# design.net
KiCad netlist of a schematic drawn in Altium Designer
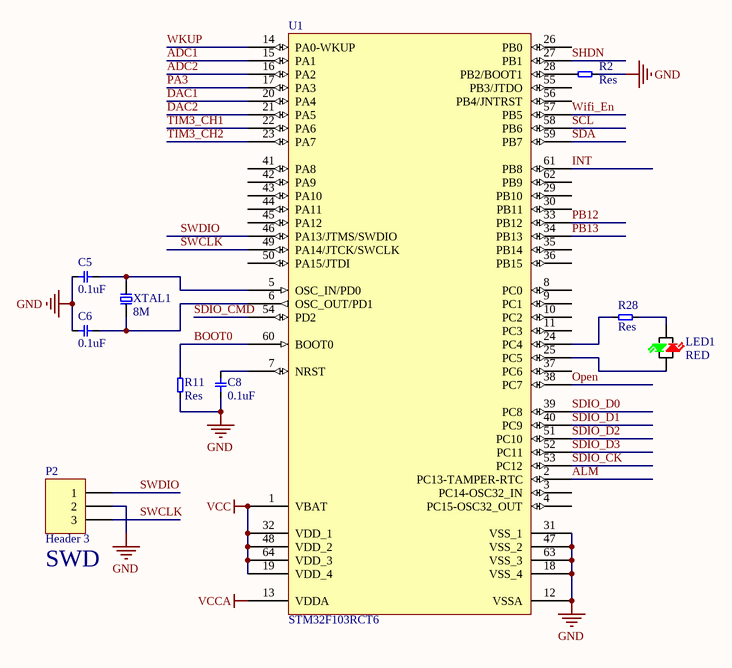
[diagram p0: 原理图.SchDoc]

(export (version "E")
  (design (tool "Eeschema 10.0.6"))
  (components
    (comp (ref "C5") (value "0.1uF") (footprint "0603") (libsource (lib "MySchLib") (part "C0.1uF")))
    (comp (ref "C6") (value "0.1uF") (footprint "0603") (libsource (lib "MySchLib") (part "C0.1uF")))
    (comp (ref "C8") (value "0.1uF") (footprint "0603") (libsource (lib "MySchLib") (part "C0.1uF")))
    (comp (ref "LED1") (value "RED") (footprint "LED2") (libsource (lib "MySchLib") (part "LED_2")))
    (comp (ref "P2")
      (value "Header 3")
      (footprint "HDR1X3-150")
      (description "Header, 3-Pin")
      (fields (field (name "PUBLISHER") "Altium Limited"))
      (libsource (lib "Miscellaneous Connectors") (part "Header 3"))
    )
    (comp (ref "R2") (value "Res") (footprint "0603") (libsource (lib "MySchLib") (part "Res")))
    (comp (ref "R11") (value "Res") (footprint "0603") (libsource (lib "MySchLib") (part "Res")))
    (comp (ref "R28") (value "Res") (footprint "0603") (libsource (lib "MySchLib") (part "Res")))
    (comp (ref "U1")
      (value "STM32F103RCT6")
      (footprint "LQFP64_N")
      (description "STM32 ARM-based 32-bit MCU with 128 Kbytes Flash, 64-pin LQFP, Industrial Temperature")
      (fields (field (name "PUBLISHER") "Altium Limited"))
      (libsource (lib "ST Microcontroller 32-Bit STM32") (part "STM32F103RBT6"))
    )
    (comp (ref "XTAL1") (value "8M") (footprint "XTAL") (libsource (lib "MySchLib") (part "XTAL")))
  )
  (nets
    (net (code "1") (name "/ADC1") (class "Default")
      (node (ref "U1") (pin "15") (pinfunction "PA1_15") (pintype "bidirectional"))
    )
    (net (code "2") (name "/ADC2") (class "Default")
      (node (ref "U1") (pin "16") (pinfunction "PA2_16") (pintype "bidirectional"))
    )
    (net (code "3") (name "/ALM") (class "Default")
      (node (ref "U1") (pin "2") (pinfunction "PC13-TAMPER-RTC_2") (pintype "bidirectional"))
    )
    (net (code "4") (name "/BOOT0") (class "Default")
      (node (ref "R11") (pin "2") (pinfunction "2_2") (pintype "passive"))
      (node (ref "U1") (pin "60") (pinfunction "BOOT0_60") (pintype "input"))
    )
    (net (code "5") (name "/DAC1") (class "Default")
      (node (ref "U1") (pin "20") (pinfunction "PA4_20") (pintype "bidirectional"))
    )
    (net (code "6") (name "/DAC2") (class "Default")
      (node (ref "U1") (pin "21") (pinfunction "PA5_21") (pintype "bidirectional"))
    )
    (net (code "7") (name "/INT") (class "Default")
      (node (ref "U1") (pin "61") (pinfunction "PB8_61") (pintype "bidirectional"))
    )
    (net (code "8") (name "/Open") (class "Default")
      (node (ref "U1") (pin "38") (pinfunction "PC7_38") (pintype "bidirectional"))
    )
    (net (code "9") (name "/PA3") (class "Default")
      (node (ref "U1") (pin "17") (pinfunction "PA3_17") (pintype "bidirectional"))
    )
    (net (code "10") (name "/PB12") (class "Default")
      (node (ref "U1") (pin "33") (pinfunction "PB12_33") (pintype "bidirectional"))
    )
    (net (code "11") (name "/PB13") (class "Default")
      (node (ref "U1") (pin "34") (pinfunction "PB13_34") (pintype "bidirectional"))
    )
    (net (code "12") (name "/SCL") (class "Default")
      (node (ref "U1") (pin "58") (pinfunction "PB6_58") (pintype "bidirectional"))
    )
    (net (code "13") (name "/SDA") (class "Default")
      (node (ref "U1") (pin "59") (pinfunction "PB7_59") (pintype "bidirectional"))
    )
    (net (code "14") (name "/SDIO_CK") (class "Default")
      (node (ref "U1") (pin "53") (pinfunction "PC12_53") (pintype "bidirectional"))
    )
    (net (code "15") (name "/SDIO_CMD") (class "Default")
      (node (ref "U1") (pin "54") (pinfunction "PD2_54") (pintype "bidirectional"))
    )
    (net (code "16") (name "/SDIO_D0") (class "Default")
      (node (ref "U1") (pin "39") (pinfunction "PC8_39") (pintype "bidirectional"))
    )
    (net (code "17") (name "/SDIO_D1") (class "Default")
      (node (ref "U1") (pin "40") (pinfunction "PC9_40") (pintype "bidirectional"))
    )
    (net (code "18") (name "/SDIO_D2") (class "Default")
      (node (ref "U1") (pin "51") (pinfunction "PC10_51") (pintype "bidirectional"))
    )
    (net (code "19") (name "/SDIO_D3") (class "Default")
      (node (ref "U1") (pin "52") (pinfunction "PC11_52") (pintype "bidirectional"))
    )
    (net (code "20") (name "/SHDN") (class "Default")
      (node (ref "U1") (pin "27") (pinfunction "PB1_27") (pintype "bidirectional"))
    )
    (net (code "21") (name "/SWCLK") (class "Default")
      (node (ref "P2") (pin "3") (pinfunction "3_3") (pintype "passive"))
      (node (ref "U1") (pin "49") (pinfunction "PA14/JTCK/SWCLK_49") (pintype "bidirectional"))
    )
    (net (code "22") (name "/SWDIO") (class "Default")
      (node (ref "P2") (pin "1") (pinfunction "1_1") (pintype "passive"))
      (node (ref "U1") (pin "46") (pinfunction "PA13/JTMS/SWDIO_46") (pintype "bidirectional"))
    )
    (net (code "23") (name "/TIM3_CH1") (class "Default")
      (node (ref "U1") (pin "22") (pinfunction "PA6_22") (pintype "bidirectional"))
    )
    (net (code "24") (name "/TIM3_CH2") (class "Default")
      (node (ref "U1") (pin "23") (pinfunction "PA7_23") (pintype "bidirectional"))
    )
    (net (code "25") (name "/WKUP") (class "Default")
      (node (ref "U1") (pin "14") (pinfunction "PA0-WKUP_14") (pintype "bidirectional"))
    )
    (net (code "26") (name "/Wifi_En") (class "Default")
      (node (ref "U1") (pin "57") (pinfunction "PB5_57") (pintype "bidirectional"))
    )
    (net (code "27") (name "GND") (class "Default")
      (node (ref "C5") (pin "1") (pinfunction "1_1") (pintype "passive"))
      (node (ref "C6") (pin "1") (pinfunction "1_1") (pintype "passive"))
      (node (ref "C8") (pin "1") (pinfunction "1_1") (pintype "passive"))
      (node (ref "P2") (pin "2") (pinfunction "2_2") (pintype "passive"))
      (node (ref "R11") (pin "1") (pinfunction "1_1") (pintype "passive"))
      (node (ref "R2") (pin "2") (pinfunction "2_2") (pintype "passive"))
      (node (ref "U1") (pin "12") (pinfunction "VSSA_12") (pintype "power_in"))
      (node (ref "U1") (pin "18") (pinfunction "VSS_4_18") (pintype "power_in"))
      (node (ref "U1") (pin "31") (pinfunction "VSS_1_31") (pintype "power_in"))
      (node (ref "U1") (pin "47") (pinfunction "VSS_2_47") (pintype "power_in"))
      (node (ref "U1") (pin "63") (pinfunction "VSS_3_63") (pintype "power_in"))
    )
    (net (code "28") (name "Net-(LED1-Pad1)") (class "Default")
      (node (ref "LED1") (pin "1") (pinfunction "1_1") (pintype "passive"))
      (node (ref "R28") (pin "2") (pinfunction "2_2") (pintype "passive"))
    )
    (net (code "29") (name "Net-(U1-NRST)") (class "Default")
      (node (ref "C8") (pin "2") (pinfunction "2_2") (pintype "passive"))
      (node (ref "U1") (pin "7") (pinfunction "NRST_7") (pintype "bidirectional"))
    )
    (net (code "30") (name "Net-(U1-OSC_IN{slash}PD0)") (class "Default")
      (node (ref "C5") (pin "2") (pinfunction "2_2") (pintype "passive"))
      (node (ref "U1") (pin "5") (pinfunction "OSC_IN/PD0_5") (pintype "input"))
      (node (ref "XTAL1") (pin "2") (pinfunction "2_2") (pintype "passive"))
    )
    (net (code "31") (name "Net-(U1-OSC_OUT{slash}PD1)") (class "Default")
      (node (ref "C6") (pin "2") (pinfunction "2_2") (pintype "passive"))
      (node (ref "U1") (pin "6") (pinfunction "OSC_OUT/PD1_6") (pintype "output"))
      (node (ref "XTAL1") (pin "1") (pinfunction "1_1") (pintype "passive"))
    )
    (net (code "32") (name "Net-(U1-PB2{slash}BOOT1)") (class "Default")
      (node (ref "R2") (pin "1") (pinfunction "1_1") (pintype "passive"))
      (node (ref "U1") (pin "28") (pinfunction "PB2/BOOT1_28") (pintype "bidirectional"))
    )
    (net (code "33") (name "Net-(U1-PC4)") (class "Default")
      (node (ref "R28") (pin "1") (pinfunction "1_1") (pintype "passive"))
      (node (ref "U1") (pin "24") (pinfunction "PC4_24") (pintype "bidirectional"))
    )
    (net (code "34") (name "Net-(U1-PC5)") (class "Default")
      (node (ref "LED1") (pin "2") (pinfunction "2_2") (pintype "passive"))
      (node (ref "U1") (pin "25") (pinfunction "PC5_25") (pintype "bidirectional"))
    )
    (net (code "35") (name "VCC") (class "Default")
      (node (ref "U1") (pin "1") (pinfunction "VBAT_1") (pintype "power_in"))
      (node (ref "U1") (pin "19") (pinfunction "VDD_4_19") (pintype "power_in"))
      (node (ref "U1") (pin "32") (pinfunction "VDD_1_32") (pintype "power_in"))
      (node (ref "U1") (pin "48") (pinfunction "VDD_2_48") (pintype "power_in"))
      (node (ref "U1") (pin "64") (pinfunction "VDD_3_64") (pintype "power_in"))
    )
    (net (code "36") (name "VCCA") (class "Default")
      (node (ref "U1") (pin "13") (pinfunction "VDDA_13") (pintype "power_in"))
    )
    (net (code "37") (name "unconnected-(U1-PA8-Pad41)") (class "Default")
      (node (ref "U1") (pin "41") (pinfunction "PA8_41") (pintype "bidirectional"))
    )
    (net (code "38") (name "unconnected-(U1-PA9-Pad42)") (class "Default")
      (node (ref "U1") (pin "42") (pinfunction "PA9_42") (pintype "bidirectional"))
    )
    (net (code "39") (name "unconnected-(U1-PA10-Pad43)") (class "Default")
      (node (ref "U1") (pin "43") (pinfunction "PA10_43") (pintype "bidirectional"))
    )
    (net (code "40") (name "unconnected-(U1-PA11-Pad44)") (class "Default")
      (node (ref "U1") (pin "44") (pinfunction "PA11_44") (pintype "bidirectional"))
    )
    (net (code "41") (name "unconnected-(U1-PA12-Pad45)") (class "Default")
      (node (ref "U1") (pin "45") (pinfunction "PA12_45") (pintype "bidirectional"))
    )
    (net (code "42") (name "unconnected-(U1-PA15{slash}JTDI-Pad50)") (class "Default")
      (node (ref "U1") (pin "50") (pinfunction "PA15/JTDI_50") (pintype "bidirectional"))
    )
    (net (code "43") (name "unconnected-(U1-PB0-Pad26)") (class "Default")
      (node (ref "U1") (pin "26") (pinfunction "PB0_26") (pintype "bidirectional"))
    )
    (net (code "44") (name "unconnected-(U1-PB3{slash}JTDO-Pad55)") (class "Default")
      (node (ref "U1") (pin "55") (pinfunction "PB3/JTDO_55") (pintype "bidirectional"))
    )
    (net (code "45") (name "unconnected-(U1-PB4{slash}JNTRST-Pad56)") (class "Default")
      (node (ref "U1") (pin "56") (pinfunction "PB4/JNTRST_56") (pintype "bidirectional"))
    )
    (net (code "46") (name "unconnected-(U1-PB9-Pad62)") (class "Default")
      (node (ref "U1") (pin "62") (pinfunction "PB9_62") (pintype "bidirectional"))
    )
    (net (code "47") (name "unconnected-(U1-PB10-Pad29)") (class "Default")
      (node (ref "U1") (pin "29") (pinfunction "PB10_29") (pintype "bidirectional"))
    )
    (net (code "48") (name "unconnected-(U1-PB11-Pad30)") (class "Default")
      (node (ref "U1") (pin "30") (pinfunction "PB11_30") (pintype "bidirectional"))
    )
    (net (code "49") (name "unconnected-(U1-PB14-Pad35)") (class "Default")
      (node (ref "U1") (pin "35") (pinfunction "PB14_35") (pintype "bidirectional"))
    )
    (net (code "50") (name "unconnected-(U1-PB15-Pad36)") (class "Default")
      (node (ref "U1") (pin "36") (pinfunction "PB15_36") (pintype "bidirectional"))
    )
    (net (code "51") (name "unconnected-(U1-PC0-Pad8)") (class "Default")
      (node (ref "U1") (pin "8") (pinfunction "PC0_8") (pintype "bidirectional"))
    )
    (net (code "52") (name "unconnected-(U1-PC1-Pad9)") (class "Default")
      (node (ref "U1") (pin "9") (pinfunction "PC1_9") (pintype "bidirectional"))
    )
    (net (code "53") (name "unconnected-(U1-PC2-Pad10)") (class "Default")
      (node (ref "U1") (pin "10") (pinfunction "PC2_10") (pintype "bidirectional"))
    )
    (net (code "54") (name "unconnected-(U1-PC3-Pad11)") (class "Default")
      (node (ref "U1") (pin "11") (pinfunction "PC3_11") (pintype "bidirectional"))
    )
    (net (code "55") (name "unconnected-(U1-PC6-Pad37)") (class "Default")
      (node (ref "U1") (pin "37") (pinfunction "PC6_37") (pintype "bidirectional"))
    )
    (net (code "56") (name "unconnected-(U1-PC14-OSC32_IN-Pad3)") (class "Default")
      (node (ref "U1") (pin "3") (pinfunction "PC14-OSC32_IN_3") (pintype "bidirectional"))
    )
    (net (code "57") (name "unconnected-(U1-PC15-OSC32_OUT-Pad4)") (class "Default")
      (node (ref "U1") (pin "4") (pinfunction "PC15-OSC32_OUT_4") (pintype "bidirectional"))
    )
  )
)
